# SparkFun_XBee3_Cat1_Smart_Modem_USB-C.net
KiCad netlist of a schematic drawn in EAGLE
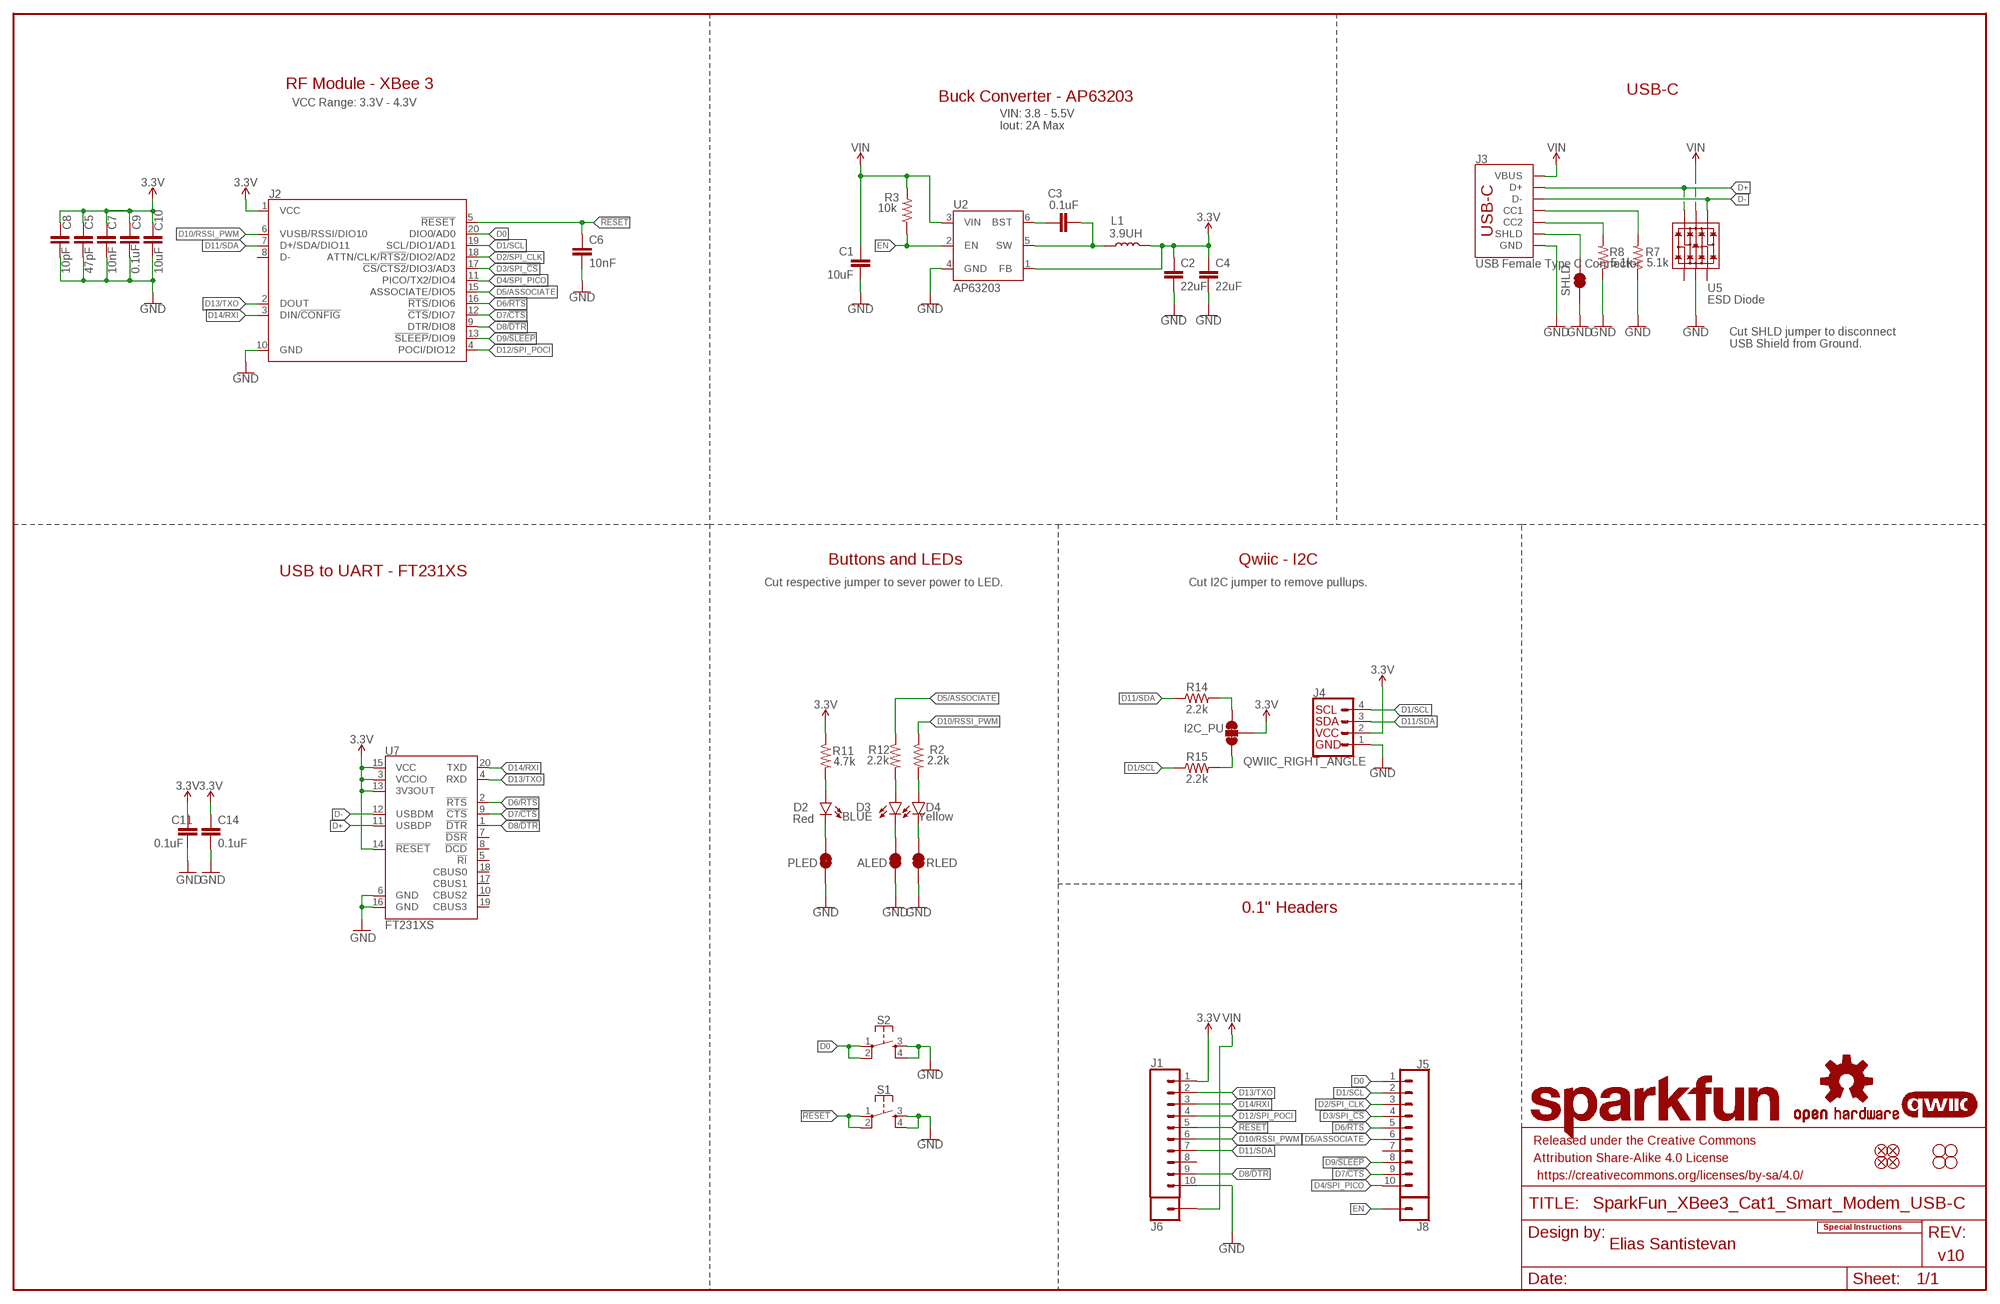
[diagram p0: schematic, sheet 1]

(export (version "E")
  (design (tool "Eeschema 10.0.6"))
  (components
    (comp (ref "ALED")
      (value "JUMPER-SMT_2_NC_TRACE_SILK")
      (footprint "eagle-import:SMT-JUMPER_2_NC_TRACE_SILK")
      (libsource (lib "eagle-import") (part "JUMPER-SMT_2_NC_TRACE_SILK"))
    )
    (comp (ref "C1")
      (value "10uF")
      (footprint "eagle-import:1210")
      (libsource (lib "eagle-import") (part "10UF-1210-50V-20%"))
    )
    (comp (ref "C2")
      (value "22uF")
      (footprint "eagle-import:0603")
      (libsource (lib "eagle-import") (part "22UF-0603-6.3V-20%"))
    )
    (comp (ref "C3")
      (value "0.1uF")
      (footprint "eagle-import:0603")
      (libsource (lib "eagle-import") (part "0.1UF-0603-25V-5%"))
    )
    (comp (ref "C4")
      (value "22uF")
      (footprint "eagle-import:0603")
      (libsource (lib "eagle-import") (part "22UF-0603-6.3V-20%"))
    )
    (comp (ref "C5")
      (value "47pF")
      (footprint "eagle-import:0603")
      (libsource (lib "eagle-import") (part "47PF-0603-50V-5%"))
    )
    (comp (ref "C6")
      (value "10nF")
      (footprint "eagle-import:0603")
      (libsource (lib "eagle-import") (part "10NF-0603-50V-10%"))
    )
    (comp (ref "C7")
      (value "10nF")
      (footprint "eagle-import:0603")
      (libsource (lib "eagle-import") (part "10NF-0603-50V-10%"))
    )
    (comp (ref "C8")
      (value "10pF")
      (footprint "eagle-import:0603")
      (libsource (lib "eagle-import") (part "10PF-0603-50V-5%"))
    )
    (comp (ref "C9")
      (value "0.1uF")
      (footprint "eagle-import:0603")
      (libsource (lib "eagle-import") (part "0.1UF-0603-25V-(+80/-20%)"))
    )
    (comp (ref "C10")
      (value "10uF")
      (footprint "eagle-import:0603")
      (libsource (lib "eagle-import") (part "10UF-0603-6.3V-20%"))
    )
    (comp (ref "C11")
      (value "0.1uF")
      (footprint "eagle-import:0603")
      (libsource (lib "eagle-import") (part "0.1UF-0603-25V-(+80/-20%)"))
    )
    (comp (ref "C14")
      (value "0.1uF")
      (footprint "eagle-import:0603")
      (libsource (lib "eagle-import") (part "0.1UF-0603-25V-(+80/-20%)"))
    )
    (comp (ref "D2")
      (value "Red")
      (footprint "eagle-import:LED-0603")
      (libsource (lib "eagle-import") (part "LED-RED-0603-WE"))
    )
    (comp (ref "D3")
      (value "BLUE")
      (footprint "eagle-import:LED-0603")
      (libsource (lib "eagle-import") (part "LED-BLUE0603"))
    )
    (comp (ref "D4")
      (value "Yellow")
      (footprint "eagle-import:LED-0603")
      (libsource (lib "eagle-import") (part "LED-YELLOW0603"))
    )
    (comp (ref "FD1")
      (value "FIDUCIAL1X2")
      (footprint "eagle-import:FIDUCIAL-1X2")
      (libsource (lib "eagle-import") (part "FIDUCIAL1X2"))
    )
    (comp (ref "FD2")
      (value "FIDUCIAL1X2")
      (footprint "eagle-import:FIDUCIAL-1X2")
      (libsource (lib "eagle-import") (part "FIDUCIAL1X2"))
    )
    (comp (ref "FD3")
      (value "FIDUCIAL1X2")
      (footprint "eagle-import:FIDUCIAL-1X2")
      (libsource (lib "eagle-import") (part "FIDUCIAL1X2"))
    )
    (comp (ref "FD4")
      (value "FIDUCIAL1X2")
      (footprint "eagle-import:FIDUCIAL-1X2")
      (libsource (lib "eagle-import") (part "FIDUCIAL1X2"))
    )
    (comp (ref "FRAME1")
      (value "FRAME-LEDGER")
      (footprint "eagle-import:CREATIVE_COMMONS")
      (libsource (lib "eagle-import") (part "FRAME-LEDGER"))
    )
    (comp (ref "H1")
      (value "STAND-OFFTIGHT")
      (footprint "eagle-import:STAND-OFF-TIGHT")
      (libsource (lib "eagle-import") (part "STAND-OFFTIGHT"))
    )
    (comp (ref "H2")
      (value "STAND-OFFTIGHT")
      (footprint "eagle-import:STAND-OFF-TIGHT")
      (libsource (lib "eagle-import") (part "STAND-OFFTIGHT"))
    )
    (comp (ref "H3")
      (value "STAND-OFFTIGHT")
      (footprint "eagle-import:STAND-OFF-TIGHT")
      (libsource (lib "eagle-import") (part "STAND-OFFTIGHT"))
    )
    (comp (ref "H4")
      (value "STAND-OFFTIGHT")
      (footprint "eagle-import:STAND-OFF-TIGHT")
      (libsource (lib "eagle-import") (part "STAND-OFFTIGHT"))
    )
    (comp (ref "I2C_PU")
      (value "JUMPER-SMT_3_2-NC_TRACE_SILK")
      (footprint "eagle-import:SMT-JUMPER_3_2-NC_TRACE_SILK")
      (libsource (lib "eagle-import") (part "JUMPER-SMT_3_2-NC_TRACE_SILK"))
    )
    (comp (ref "J1")
      (value "CONN_01PTH_NO_SILK_STAND")
      (footprint "eagle-import:1X01_NO_SILK_STAND")
      (libsource (lib "eagle-import") (part "CONN_01PTH_NO_SILK_STAND"))
    )
    (comp (ref "J2")
      (value "XBEE_UPDATEXBEE_SMD")
      (footprint "eagle-import:XBEE3-SMD")
      (libsource (lib "eagle-import") (part "XBEE_UPDATEXBEE_SMD"))
    )
    (comp (ref "J3")
      (value "USB Female Type C Connector")
      (footprint "eagle-import:USB-C-16P-4LAYER-ISOLATED")
      (libsource (lib "eagle-import") (part "USB_C_4-LAYER-ISOLATED"))
    )
    (comp (ref "J4")
      (value "QWIIC_RIGHT_ANGLE")
      (footprint "eagle-import:JST04_1MM_RA")
      (libsource (lib "eagle-import") (part "QWIIC_CONNECTORJS-1MM"))
    )
    (comp (ref "J5")
      (value "CONN_10NO_SILK_PTH_FEMALE")
      (footprint "eagle-import:1X10_NO_SILK")
      (libsource (lib "eagle-import") (part "CONN_10NO_SILK_PTH_FEMALE"))
    )
    (comp (ref "J6")
      (value "CONN_10NO_SILK_PTH_FEMALE")
      (footprint "eagle-import:1X10_NO_SILK")
      (libsource (lib "eagle-import") (part "CONN_10NO_SILK_PTH_FEMALE"))
    )
    (comp (ref "J8")
      (value "CONN_01PTH_NO_SILK_STAND")
      (footprint "eagle-import:1X01_NO_SILK_STAND")
      (libsource (lib "eagle-import") (part "CONN_01PTH_NO_SILK_STAND"))
    )
    (comp (ref "L1")
      (value "3.9UH")
      (footprint "eagle-import:INDUCTOR_3.9UH")
      (libsource (lib "eagle-import") (part "3.9UH"))
    )
    (comp (ref "LOGO1")
      (value "SFE_LOGO_NAME.2_INCH")
      (footprint "eagle-import:SFE_LOGO_NAME_.2")
      (libsource (lib "eagle-import") (part "SFE_LOGO_NAME.2_INCH"))
    )
    (comp (ref "LOGO2")
      (value "OSHW-LOGOS")
      (footprint "eagle-import:OSHW-LOGO-S")
      (libsource (lib "eagle-import") (part "OSHW-LOGOS"))
    )
    (comp (ref "LOGO3")
      (value "QWIIC_LOGO_3MM")
      (footprint "eagle-import:QWIIC_3MM")
      (libsource (lib "eagle-import") (part "QWIIC_LOGO_3MM"))
    )
    (comp (ref "LOGO4")
      (value "SPECIAL_INSTRUCTIONS-ORDERING")
      (footprint "eagle-import:ORDERING_INSTRUCTIONS")
      (libsource (lib "eagle-import") (part "SPECIAL_INSTRUCTIONS-ORDERING"))
    )
    (comp (ref "PLED")
      (value "JUMPER-SMT_2_NC_TRACE_SILK")
      (footprint "eagle-import:SMT-JUMPER_2_NC_TRACE_SILK")
      (libsource (lib "eagle-import") (part "JUMPER-SMT_2_NC_TRACE_SILK"))
    )
    (comp (ref "R2")
      (value "2.2k")
      (footprint "eagle-import:0603")
      (libsource (lib "eagle-import") (part "2.2KOHM-0603-1/10W-1%"))
    )
    (comp (ref "R3")
      (value "10k")
      (footprint "eagle-import:0603")
      (libsource (lib "eagle-import") (part "10KOHM-0603-1/10W-1%"))
    )
    (comp (ref "R7")
      (value "5.1k")
      (footprint "eagle-import:0603")
      (libsource (lib "eagle-import") (part "5.1KOHM5.1KOHM-0603-1/10W-1%"))
    )
    (comp (ref "R8")
      (value "5.1k")
      (footprint "eagle-import:0603")
      (libsource (lib "eagle-import") (part "5.1KOHM5.1KOHM-0603-1/10W-1%"))
    )
    (comp (ref "R11")
      (value "4.7k")
      (footprint "eagle-import:0603")
      (libsource (lib "eagle-import") (part "4.7KOHM-0603-1/10W-1%"))
    )
    (comp (ref "R12")
      (value "2.2k")
      (footprint "eagle-import:0603")
      (libsource (lib "eagle-import") (part "2.2KOHM-0603-1/10W-1%"))
    )
    (comp (ref "R14")
      (value "2.2k")
      (footprint "eagle-import:0603")
      (libsource (lib "eagle-import") (part "2.2KOHM-0603-1/10W-1%"))
    )
    (comp (ref "R15")
      (value "2.2k")
      (footprint "eagle-import:0603")
      (libsource (lib "eagle-import") (part "2.2KOHM-0603-1/10W-1%"))
    )
    (comp (ref "RLED")
      (value "JUMPER-SMT_2_NC_TRACE_SILK")
      (footprint "eagle-import:SMT-JUMPER_2_NC_TRACE_SILK")
      (libsource (lib "eagle-import") (part "JUMPER-SMT_2_NC_TRACE_SILK"))
    )
    (comp (ref "S1")
      (value "MOMENTARY-SWITCH-SPST-2-SMD-5.2MM-TALL")
      (footprint "eagle-import:TACTILE_SWITCH_SMD_5.2MM")
      (libsource (lib "eagle-import") (part "MOMENTARY-SWITCH-SPST-2-SMD-5.2MM-TALL"))
    )
    (comp (ref "S2")
      (value "MOMENTARY-SWITCH-SPST-2-SMD-5.2MM-TALL")
      (footprint "eagle-import:TACTILE_SWITCH_SMD_5.2MM")
      (libsource (lib "eagle-import") (part "MOMENTARY-SWITCH-SPST-2-SMD-5.2MM-TALL"))
    )
    (comp (ref "SHLD")
      (value "JUMPER-SMT_2_NC_TRACE_SILK")
      (footprint "eagle-import:SMT-JUMPER_2_NC_TRACE_SILK")
      (libsource (lib "eagle-import") (part "JUMPER-SMT_2_NC_TRACE_SILK"))
    )
    (comp (ref "U2")
      (value "AP63203")
      (footprint "eagle-import:SOT23-6")
      (libsource (lib "eagle-import") (part "AP63203"))
    )
    (comp (ref "U5")
      (value "ESD Diode")
      (footprint "eagle-import:SOT-23-6")
      (libsource (lib "eagle-import") (part "TVS_DIODE_ARRAY_DT1042-04SO-7"))
    )
    (comp (ref "U7")
      (value "FT231XS")
      (footprint "eagle-import:SSOP20_L")
      (libsource (lib "eagle-import") (part "FT231XS"))
    )
  )
  (nets
    (net (code "1") (name "/D3{slash}SPI_~{CS}") (class "Default")
      (node (ref "J2") (pin "17") (pinfunction "~{CS}/~{CTS2}/DIO3/AD3_17") (pintype "bidirectional"))
      (node (ref "J5") (pin "4") (pinfunction "4_4") (pintype "passive"))
    )
    (net (code "2") (name "/D6{slash}~{RTS}") (class "Default")
      (node (ref "J2") (pin "16") (pinfunction "~{RTS}/DIO6_16") (pintype "input"))
      (node (ref "J5") (pin "5") (pinfunction "5_5") (pintype "passive"))
      (node (ref "U7") (pin "2") (pinfunction "~{RTS}_2") (pintype "bidirectional"))
    )
    (net (code "3") (name "/D7{slash}~{CTS}") (class "Default")
      (node (ref "J2") (pin "12") (pinfunction "~{CTS}/DIO7_12") (pintype "output"))
      (node (ref "J5") (pin "9") (pinfunction "9_9") (pintype "passive"))
      (node (ref "U7") (pin "9") (pinfunction "~{CTS}_9") (pintype "bidirectional"))
    )
    (net (code "4") (name "/D8{slash}~{DTR}") (class "Default")
      (node (ref "J2") (pin "9") (pinfunction "DTR/DIO8_9") (pintype "bidirectional"))
      (node (ref "J6") (pin "9") (pinfunction "9_9") (pintype "passive"))
      (node (ref "U7") (pin "1") (pinfunction "~{DTR}_1") (pintype "bidirectional"))
    )
    (net (code "5") (name "/D9{slash}~{SLEEP}") (class "Default")
      (node (ref "J2") (pin "13") (pinfunction "~{SLEEP}/DIO9_13") (pintype "bidirectional"))
      (node (ref "J5") (pin "8") (pinfunction "8_8") (pintype "passive"))
    )
    (net (code "6") (name "/~{RESET}") (class "Default")
      (node (ref "C6") (pin "1") (pinfunction "1_1") (pintype "passive"))
      (node (ref "J2") (pin "5") (pinfunction "~{RESET}_5") (pintype "input"))
      (node (ref "J6") (pin "5") (pinfunction "5_5") (pintype "passive"))
      (node (ref "S1") (pin "1") (pinfunction "1_1") (pintype "passive"))
      (node (ref "S1") (pin "2") (pinfunction "2_2") (pintype "passive"))
    )
    (net (code "7") (name "3.3V") (class "Default")
      (node (ref "C10") (pin "1") (pinfunction "1_1") (pintype "passive"))
      (node (ref "C11") (pin "1") (pinfunction "1_1") (pintype "passive"))
      (node (ref "C14") (pin "1") (pinfunction "1_1") (pintype "passive"))
      (node (ref "C2") (pin "1") (pinfunction "1_1") (pintype "passive"))
      (node (ref "C4") (pin "1") (pinfunction "1_1") (pintype "passive"))
      (node (ref "C5") (pin "1") (pinfunction "1_1") (pintype "passive"))
      (node (ref "C7") (pin "1") (pinfunction "1_1") (pintype "passive"))
      (node (ref "C8") (pin "1") (pinfunction "1_1") (pintype "passive"))
      (node (ref "C9") (pin "1") (pinfunction "1_1") (pintype "passive"))
      (node (ref "I2C_PU") (pin "2") (pinfunction "2_2") (pintype "passive"))
      (node (ref "J2") (pin "1") (pinfunction "VCC_1") (pintype "power_in"))
      (node (ref "J4") (pin "2") (pinfunction "2_2") (pintype "power_in"))
      (node (ref "J6") (pin "1") (pinfunction "1_1") (pintype "passive"))
      (node (ref "L1") (pin "P$2") (pinfunction "2_P$2") (pintype "passive"))
      (node (ref "R11") (pin "1") (pinfunction "1_1") (pintype "passive"))
      (node (ref "U2") (pin "1") (pinfunction "FB_1") (pintype "bidirectional"))
      (node (ref "U7") (pin "13") (pinfunction "3V3OUT_13") (pintype "bidirectional"))
      (node (ref "U7") (pin "14") (pinfunction "~{RESET}_14") (pintype "bidirectional"))
      (node (ref "U7") (pin "15") (pinfunction "VCC_15") (pintype "bidirectional"))
      (node (ref "U7") (pin "3") (pinfunction "VCCIO_3") (pintype "bidirectional"))
    )
    (net (code "8") (name "D+") (class "Default")
      (node (ref "J3") (pin "A6") (pinfunction "D+_A6") (pintype "bidirectional"))
      (node (ref "J3") (pin "B6") (pinfunction "D+_B6") (pintype "bidirectional"))
      (node (ref "U5") (pin "6") (pinfunction "IO4_6") (pintype "bidirectional"))
      (node (ref "U7") (pin "11") (pinfunction "USBDP_11") (pintype "bidirectional"))
    )
    (net (code "9") (name "D-") (class "Default")
      (node (ref "J3") (pin "A7") (pinfunction "D-_A7") (pintype "bidirectional"))
      (node (ref "J3") (pin "B7") (pinfunction "D-_B7") (pintype "bidirectional"))
      (node (ref "U5") (pin "4") (pinfunction "IO3_4") (pintype "bidirectional"))
      (node (ref "U7") (pin "12") (pinfunction "USBDM_12") (pintype "bidirectional"))
    )
    (net (code "10") (name "D0") (class "Default")
      (node (ref "J2") (pin "20") (pinfunction "DIO0/AD0_20") (pintype "bidirectional"))
      (node (ref "J5") (pin "1") (pinfunction "1_1") (pintype "passive"))
      (node (ref "S2") (pin "1") (pinfunction "1_1") (pintype "passive"))
      (node (ref "S2") (pin "2") (pinfunction "2_2") (pintype "passive"))
    )
    (net (code "11") (name "D1{slash}SCL") (class "Default")
      (node (ref "J2") (pin "19") (pinfunction "SCL/DIO1/AD1_19") (pintype "bidirectional"))
      (node (ref "J4") (pin "4") (pinfunction "4_4") (pintype "passive"))
      (node (ref "J5") (pin "2") (pinfunction "2_2") (pintype "passive"))
      (node (ref "R15") (pin "1") (pinfunction "1_1") (pintype "passive"))
    )
    (net (code "12") (name "D2{slash}SPI_CLK") (class "Default")
      (node (ref "J2") (pin "18") (pinfunction "ATTN/CLK/~{RTS2}/DIO2/AD2_18") (pintype "bidirectional"))
      (node (ref "J5") (pin "3") (pinfunction "3_3") (pintype "passive"))
    )
    (net (code "13") (name "D4{slash}SPI_PICO") (class "Default")
      (node (ref "J2") (pin "11") (pinfunction "PICO/TX2/DIO4_11") (pintype "bidirectional"))
      (node (ref "J5") (pin "10") (pinfunction "10_10") (pintype "passive"))
    )
    (net (code "14") (name "D5{slash}ASSOCIATE") (class "Default")
      (node (ref "J2") (pin "15") (pinfunction "ASSOCIATE/DIO5_15") (pintype "bidirectional"))
      (node (ref "J5") (pin "6") (pinfunction "6_6") (pintype "passive"))
      (node (ref "R12") (pin "1") (pinfunction "1_1") (pintype "passive"))
    )
    (net (code "15") (name "D10{slash}RSSI_PWM") (class "Default")
      (node (ref "J2") (pin "6") (pinfunction "VUSB/RSSI/DIO10_6") (pintype "bidirectional"))
      (node (ref "J6") (pin "6") (pinfunction "6_6") (pintype "passive"))
      (node (ref "R2") (pin "1") (pinfunction "1_1") (pintype "passive"))
    )
    (net (code "16") (name "D11{slash}SDA") (class "Default")
      (node (ref "J2") (pin "7") (pinfunction "D+/SDA/DIO11_7") (pintype "bidirectional"))
      (node (ref "J4") (pin "3") (pinfunction "3_3") (pintype "passive"))
      (node (ref "J6") (pin "7") (pinfunction "7_7") (pintype "passive"))
      (node (ref "R14") (pin "1") (pinfunction "1_1") (pintype "passive"))
    )
    (net (code "17") (name "D12{slash}SPI_POCI") (class "Default")
      (node (ref "J2") (pin "4") (pinfunction "POCI/DIO12_4") (pintype "bidirectional"))
      (node (ref "J6") (pin "4") (pinfunction "4_4") (pintype "passive"))
    )
    (net (code "18") (name "D13{slash}TXO") (class "Default")
      (node (ref "J2") (pin "2") (pinfunction "DOUT_2") (pintype "output"))
      (node (ref "J6") (pin "2") (pinfunction "2_2") (pintype "passive"))
      (node (ref "U7") (pin "4") (pinfunction "RXD_4") (pintype "bidirectional"))
    )
    (net (code "19") (name "D14{slash}RXI") (class "Default")
      (node (ref "J2") (pin "3") (pinfunction "DIN/~{CONFIG}_3") (pintype "input"))
      (node (ref "J6") (pin "3") (pinfunction "3_3") (pintype "passive"))
      (node (ref "U7") (pin "20") (pinfunction "TXD_20") (pintype "bidirectional"))
    )
    (net (code "20") (name "EN") (class "Default")
      (node (ref "J8") (pin "1") (pinfunction "1_1") (pintype "passive"))
      (node (ref "R3") (pin "1") (pinfunction "1_1") (pintype "passive"))
      (node (ref "U2") (pin "2") (pinfunction "EN_2") (pintype "bidirectional"))
    )
    (net (code "21") (name "GND") (class "Default")
      (node (ref "ALED") (pin "1") (pinfunction "1_1") (pintype "passive"))
      (node (ref "C1") (pin "2") (pinfunction "2_2") (pintype "passive"))
      (node (ref "C10") (pin "2") (pinfunction "2_2") (pintype "passive"))
      (node (ref "C11") (pin "2") (pinfunction "2_2") (pintype "passive"))
      (node (ref "C14") (pin "2") (pinfunction "2_2") (pintype "passive"))
      (node (ref "C2") (pin "2") (pinfunction "2_2") (pintype "passive"))
      (node (ref "C4") (pin "2") (pinfunction "2_2") (pintype "passive"))
      (node (ref "C5") (pin "2") (pinfunction "2_2") (pintype "passive"))
      (node (ref "C6") (pin "2") (pinfunction "2_2") (pintype "passive"))
      (node (ref "C7") (pin "2") (pinfunction "2_2") (pintype "passive"))
      (node (ref "C8") (pin "2") (pinfunction "2_2") (pintype "passive"))
      (node (ref "C9") (pin "2") (pinfunction "2_2") (pintype "passive"))
      (node (ref "J2") (pin "10") (pinfunction "GND_10") (pintype "power_in"))
      (node (ref "J3") (pin "GND") (pinfunction "GND_GND") (pintype "bidirectional"))
      (node (ref "J3") (pin "GND2") (pinfunction "GND_GND2") (pintype "bidirectional"))
      (node (ref "J4") (pin "1") (pinfunction "1_1") (pintype "power_in"))
      (node (ref "J6") (pin "10") (pinfunction "10_10") (pintype "passive"))
      (node (ref "PLED") (pin "1") (pinfunction "1_1") (pintype "passive"))
      (node (ref "R7") (pin "1") (pinfunction "1_1") (pintype "passive"))
      (node (ref "R8") (pin "1") (pinfunction "1_1") (pintype "passive"))
      (node (ref "RLED") (pin "1") (pinfunction "1_1") (pintype "passive"))
      (node (ref "S1") (pin "3") (pinfunction "3_3") (pintype "passive"))
      (node (ref "S1") (pin "4") (pinfunction "4_4") (pintype "passive"))
      (node (ref "S2") (pin "3") (pinfunction "3_3") (pintype "passive"))
      (node (ref "S2") (pin "4") (pinfunction "4_4") (pintype "passive"))
      (node (ref "SHLD") (pin "1") (pinfunction "1_1") (pintype "passive"))
      (node (ref "U2") (pin "4") (pinfunction "GND_4") (pintype "bidirectional"))
      (node (ref "U5") (pin "2") (pinfunction "VSS_2") (pintype "bidirectional"))
      (node (ref "U7") (pin "16") (pinfunction "GND_16") (pintype "bidirectional"))
      (node (ref "U7") (pin "6") (pinfunction "GND_6") (pintype "bidirectional"))
    )
    (net (code "22") (name "Net-(ALED-Pad2)") (class "Default")
      (node (ref "ALED") (pin "2") (pinfunction "2_2") (pintype "passive"))
      (node (ref "D3") (pin "C") (pinfunction "C_C") (pintype "passive"))
    )
    (net (code "23") (name "Net-(D2-PadA)") (class "Default")
      (node (ref "D2") (pin "A") (pinfunction "A_A") (pintype "passive"))
      (node (ref "R11") (pin "2") (pinfunction "2_2") (pintype "passive"))
    )
    (net (code "24") (name "Net-(D2-PadC)") (class "Default")
      (node (ref "D2") (pin "C") (pinfunction "C_C") (pintype "passive"))
      (node (ref "PLED") (pin "2") (pinfunction "2_2") (pintype "passive"))
    )
    (net (code "25") (name "Net-(D3-PadA)") (class "Default")
      (node (ref "D3") (pin "A") (pinfunction "A_A") (pintype "passive"))
      (node (ref "R12") (pin "2") (pinfunction "2_2") (pintype "passive"))
    )
    (net (code "26") (name "Net-(D4-PadA)") (class "Default")
      (node (ref "D4") (pin "A") (pinfunction "A_A") (pintype "passive"))
      (node (ref "R2") (pin "2") (pinfunction "2_2") (pintype "passive"))
    )
    (net (code "27") (name "Net-(D4-PadC)") (class "Default")
      (node (ref "D4") (pin "C") (pinfunction "C_C") (pintype "passive"))
      (node (ref "RLED") (pin "2") (pinfunction "2_2") (pintype "passive"))
    )
    (net (code "28") (name "Net-(I2C_PU-Pad1)") (class "Default")
      (node (ref "I2C_PU") (pin "1") (pinfunction "1_1") (pintype "passive"))
      (node (ref "R15") (pin "2") (pinfunction "2_2") (pintype "passive"))
    )
    (net (code "29") (name "Net-(I2C_PU-Pad3)") (class "Default")
      (node (ref "I2C_PU") (pin "3") (pinfunction "3_3") (pintype "passive"))
      (node (ref "R14") (pin "2") (pinfunction "2_2") (pintype "passive"))
    )
    (net (code "30") (name "Net-(J3-CC1)") (class "Default")
      (node (ref "J3") (pin "A5") (pinfunction "CC1_A5") (pintype "bidirectional"))
      (node (ref "R7") (pin "2") (pinfunction "2_2") (pintype "passive"))
    )
    (net (code "31") (name "Net-(J3-CC2)") (class "Default")
      (node (ref "J3") (pin "B5") (pinfunction "CC2_B5") (pintype "bidirectional"))
      (node (ref "R8") (pin "2") (pinfunction "2_2") (pintype "passive"))
    )
    (net (code "32") (name "Net-(J3-SHLD-PadSHLD1)") (class "Default")
      (node (ref "J3") (pin "SHLD1") (pinfunction "SHLD_SHLD1") (pintype "bidirectional"))
      (node (ref "J3") (pin "SHLD2") (pinfunction "SHLD_SHLD2") (pintype "bidirectional"))
      (node (ref "J3") (pin "SHLD3") (pinfunction "SHLD_SHLD3") (pintype "bidirectional"))
      (node (ref "J3") (pin "SHLD4") (pinfunction "SHLD_SHLD4") (pintype "bidirectional"))
      (node (ref "J3") (pin "SHLD5") (pinfunction "SHLD_SHLD5") (pintype "bidirectional"))
      (node (ref "J3") (pin "SHLD6") (pinfunction "SHLD_SHLD6") (pintype "bidirectional"))
      (node (ref "J3") (pin "SHLD7") (pinfunction "SHLD_SHLD7") (pintype "bidirectional"))
      (node (ref "J3") (pin "SHLD8") (pinfunction "SHLD_SHLD8") (pintype "bidirectional"))
      (node (ref "SHLD") (pin "2") (pinfunction "2_2") (pintype "passive"))
    )
    (net (code "33") (name "Net-(L1-1)") (class "Default")
      (node (ref "C3") (pin "2") (pinfunction "2_2") (pintype "passive"))
      (node (ref "L1") (pin "P$1") (pinfunction "1_P$1") (pintype "passive"))
      (node (ref "U2") (pin "5") (pinfunction "SW_5") (pintype "bidirectional"))
    )
    (net (code "34") (name "Net-(U2-BST)") (class "Default")
      (node (ref "C3") (pin "1") (pinfunction "1_1") (pintype "passive"))
      (node (ref "U2") (pin "6") (pinfunction "BST_6") (pintype "bidirectional"))
    )
    (net (code "35") (name "VIN") (class "Default")
      (node (ref "C1") (pin "1") (pinfunction "1_1") (pintype "passive"))
      (node (ref "J1") (pin "1") (pinfunction "1_1") (pintype "passive"))
      (node (ref "J3") (pin "VBUS1") (pinfunction "VBUS_VBUS1") (pintype "bidirectional"))
      (node (ref "J3") (pin "VBUS2") (pinfunction "VBUS_VBUS2") (pintype "bidirectional"))
      (node (ref "R3") (pin "2") (pinfunction "2_2") (pintype "passive"))
      (node (ref "U2") (pin "3") (pinfunction "VIN_3") (pintype "bidirectional"))
      (node (ref "U5") (pin "5") (pinfunction "VCC_5") (pintype "bidirectional"))
    )
    (net (code "36") (name "unconnected-(J2-D--Pad8)") (class "Default")
      (node (ref "J2") (pin "8") (pinfunction "D-_8") (pintype "bidirectional"))
    )
    (net (code "37") (name "unconnected-(J5-Pad7)") (class "Default")
      (node (ref "J5") (pin "7") (pinfunction "7_7") (pintype "passive"))
    )
    (net (code "38") (name "unconnected-(J6-Pad8)") (class "Default")
      (node (ref "J6") (pin "8") (pinfunction "8_8") (pintype "passive"))
    )
    (net (code "39") (name "unconnected-(U5-IO1-Pad1)") (class "Default")
      (node (ref "U5") (pin "1") (pinfunction "IO1_1") (pintype "bidirectional"))
    )
    (net (code "40") (name "unconnected-(U5-IO2-Pad3)") (class "Default")
      (node (ref "U5") (pin "3") (pinfunction "IO2_3") (pintype "bidirectional"))
    )
    (net (code "41") (name "unconnected-(U7-CBUS0-Pad18)") (class "Default")
      (node (ref "U7") (pin "18") (pinfunction "CBUS0_18") (pintype "bidirectional"))
    )
    (net (code "42") (name "unconnected-(U7-CBUS1-Pad17)") (class "Default")
      (node (ref "U7") (pin "17") (pinfunction "CBUS1_17") (pintype "bidirectional"))
    )
    (net (code "43") (name "unconnected-(U7-CBUS2-Pad10)") (class "Default")
      (node (ref "U7") (pin "10") (pinfunction "CBUS2_10") (pintype "bidirectional"))
    )
    (net (code "44") (name "unconnected-(U7-CBUS3-Pad19)") (class "Default")
      (node (ref "U7") (pin "19") (pinfunction "CBUS3_19") (pintype "bidirectional"))
    )
    (net (code "45") (name "unconnected-(U7-~{DCD}-Pad8)") (class "Default")
      (node (ref "U7") (pin "8") (pinfunction "~{DCD}_8") (pintype "bidirectional"))
    )
    (net (code "46") (name "unconnected-(U7-~{DSR}-Pad7)") (class "Default")
      (node (ref "U7") (pin "7") (pinfunction "~{DSR}_7") (pintype "bidirectional"))
    )
    (net (code "47") (name "unconnected-(U7-~{RI}-Pad5)") (class "Default")
      (node (ref "U7") (pin "5") (pinfunction "~{RI}_5") (pintype "bidirectional"))
    )
  )
)
